# RederReverse.net
KiCad netlist of a schematic drawn in Altium Designer
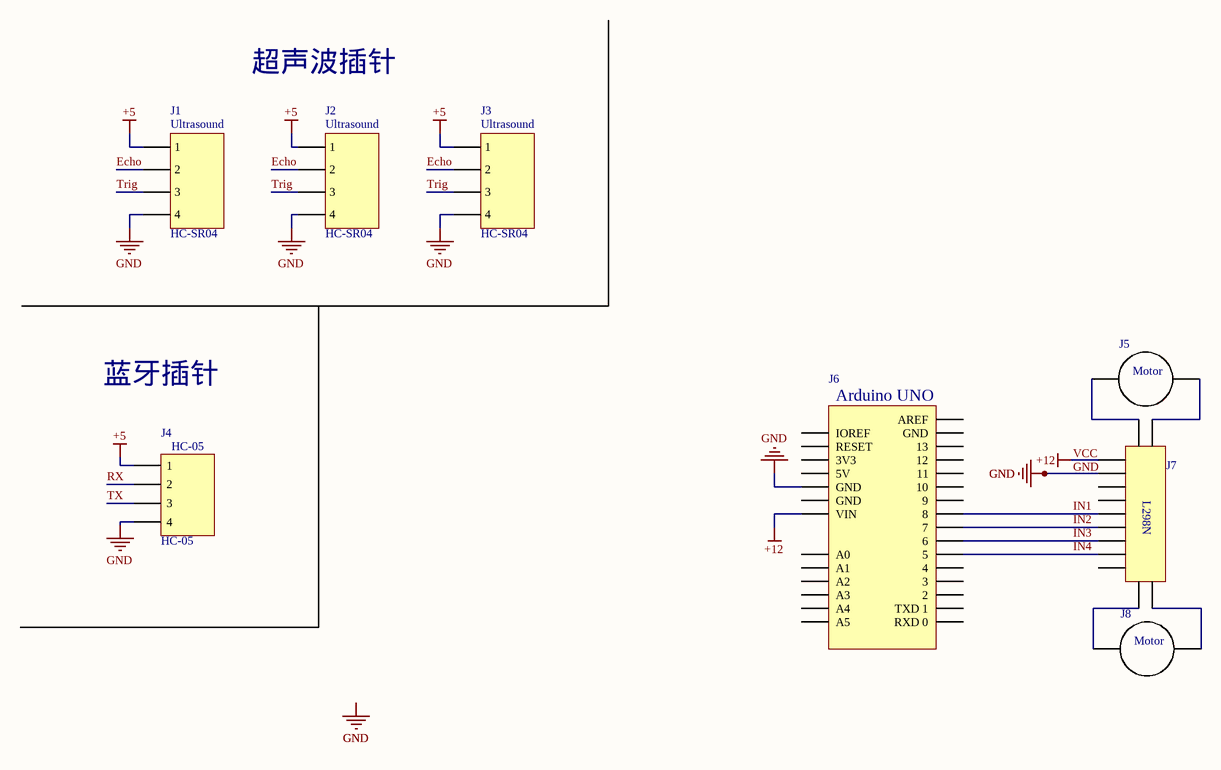
[diagram p0: RederReverse.SchDoc]

(export (version "E")
  (design (tool "Eeschema 10.0.6"))
  (components
    (comp (ref "J1")
      (value "HC-SR04")
      (description "超声波插针")
      (libsource (lib "RederReverse") (part "HC-SR04"))
    )
    (comp (ref "J2")
      (value "HC-SR04")
      (description "超声波插针")
      (libsource (lib "RederReverse") (part "HC-SR04"))
    )
    (comp (ref "J3")
      (value "HC-SR04")
      (description "超声波插针")
      (libsource (lib "RederReverse") (part "HC-SR04"))
    )
    (comp (ref "J4") (value "HC-05") (description "蓝牙插针") (libsource (lib "RederReverse") (part "HC-05")))
    (comp (ref "J5") (value "motor") (libsource (lib "RederReverse") (part "motor")))
    (comp (ref "J6") (value "A") (libsource (lib "RederReverse") (part "Arduino")))
    (comp (ref "J7") (value "L298N") (libsource (lib "RederReverse") (part "L298N")))
    (comp (ref "J8") (value "motor") (libsource (lib "RederReverse") (part "motor")))
  )
  (nets
    (net (code "1") (name "+5") (class "Default")
      (node (ref "J1") (pin "1") (pinfunction "1_1") (pintype "passive"))
      (node (ref "J2") (pin "1") (pinfunction "1_1") (pintype "passive"))
      (node (ref "J3") (pin "1") (pinfunction "1_1") (pintype "passive"))
      (node (ref "J4") (pin "1") (pinfunction "1_1") (pintype "passive"))
    )
    (net (code "2") (name "+12") (class "Default")
      (node (ref "J6") (pin "5") (pinfunction "VIN_5") (pintype "passive"))
      (node (ref "J7") (pin "4") (pinfunction "4_4") (pintype "passive"))
    )
    (net (code "3") (name "/Echo") (class "Default")
      (node (ref "J1") (pin "2") (pinfunction "2_2") (pintype "passive"))
      (node (ref "J2") (pin "2") (pinfunction "2_2") (pintype "passive"))
      (node (ref "J3") (pin "2") (pinfunction "2_2") (pintype "passive"))
    )
    (net (code "4") (name "/IN1") (class "Default")
      (node (ref "J6") (pin "14") (pinfunction "8_14") (pintype "passive"))
      (node (ref "J7") (pin "7") (pinfunction "7_7") (pintype "passive"))
    )
    (net (code "5") (name "/IN2") (class "Default")
      (node (ref "J6") (pin "13") (pinfunction "7_13") (pintype "passive"))
      (node (ref "J7") (pin "5") (pinfunction "5_5") (pintype "passive"))
    )
    (net (code "6") (name "/IN3") (class "Default")
      (node (ref "J6") (pin "12") (pinfunction "6_12") (pintype "passive"))
      (node (ref "J7") (pin "5") (pinfunction "5_5") (pintype "passive"))
    )
    (net (code "7") (name "/IN4") (class "Default")
      (node (ref "J6") (pin "11") (pinfunction "5_11") (pintype "passive"))
      (node (ref "J7") (pin "6") (pinfunction "6_6") (pintype "passive"))
    )
    (net (code "8") (name "/RX") (class "Default")
      (node (ref "J4") (pin "2") (pinfunction "2_2") (pintype "passive"))
    )
    (net (code "9") (name "/TX") (class "Default")
      (node (ref "J4") (pin "3") (pinfunction "3_3") (pintype "passive"))
    )
    (net (code "10") (name "/Trig") (class "Default")
      (node (ref "J1") (pin "3") (pinfunction "3_3") (pintype "passive"))
      (node (ref "J2") (pin "3") (pinfunction "3_3") (pintype "passive"))
      (node (ref "J3") (pin "3") (pinfunction "3_3") (pintype "passive"))
    )
    (net (code "12") (name "GND") (class "Default")
      (node (ref "J1") (pin "4") (pinfunction "4_4") (pintype "passive"))
      (node (ref "J2") (pin "4") (pinfunction "4_4") (pintype "passive"))
      (node (ref "J3") (pin "4") (pinfunction "4_4") (pintype "passive"))
      (node (ref "J4") (pin "4") (pinfunction "4_4") (pintype "passive"))
      (node (ref "J6") (pin "3") (pinfunction "GND_3") (pintype "passive"))
      (node (ref "J7") (pin "4") (pinfunction "4_4") (pintype "passive"))
    )
    (net (code "13") (name "Net-(J5-Pad1)") (class "Default")
      (node (ref "J5") (pin "1") (pinfunction "1_1") (pintype "passive"))
      (node (ref "J7") (pin "2") (pinfunction "2_2") (pintype "passive"))
    )
    (net (code "14") (name "Net-(J5-Pad2)") (class "Default")
      (node (ref "J5") (pin "2") (pinfunction "2_2") (pintype "passive"))
      (node (ref "J7") (pin "1") (pinfunction "1_1") (pintype "passive"))
    )
    (net (code "15") (name "Net-(J7-Pad3)") (class "Default")
      (node (ref "J7") (pin "3") (pinfunction "3_3") (pintype "passive"))
      (node (ref "J8") (pin "2") (pinfunction "2_2") (pintype "passive"))
    )
    (net (code "16") (name "Net-(J7-Pad4)") (class "Default")
      (node (ref "J7") (pin "4") (pinfunction "4_4") (pintype "passive"))
      (node (ref "J8") (pin "1") (pinfunction "1_1") (pintype "passive"))
    )
    (net (code "17") (name "unconnected-(J6-2-Pad8)") (class "Default")
      (node (ref "J6") (pin "8") (pinfunction "2_8") (pintype "passive"))
    )
    (net (code "18") (name "unconnected-(J6-3-Pad9)") (class "Default")
      (node (ref "J6") (pin "9") (pinfunction "3_9") (pintype "passive"))
    )
    (net (code "19") (name "unconnected-(J6-3V3-Pad4)") (class "Default")
      (node (ref "J6") (pin "4") (pinfunction "3V3_4") (pintype "passive"))
    )
    (net (code "20") (name "unconnected-(J6-4-Pad10)") (class "Default")
      (node (ref "J6") (pin "10") (pinfunction "4_10") (pintype "passive"))
    )
    (net (code "21") (name "unconnected-(J6-5V-Pad5)") (class "Default")
      (node (ref "J6") (pin "5") (pinfunction "5V_5") (pintype "passive"))
    )
    (net (code "22") (name "unconnected-(J6-9-Pad15)") (class "Default")
      (node (ref "J6") (pin "15") (pinfunction "9_15") (pintype "passive"))
    )
    (net (code "23") (name "unconnected-(J6-10-Pad16)") (class "Default")
      (node (ref "J6") (pin "16") (pinfunction "10_16") (pintype "passive"))
    )
    (net (code "24") (name "unconnected-(J6-11-Pad17)") (class "Default")
      (node (ref "J6") (pin "17") (pinfunction "11_17") (pintype "passive"))
    )
    (net (code "25") (name "unconnected-(J6-12-Pad18)") (class "Default")
      (node (ref "J6") (pin "18") (pinfunction "12_18") (pintype "passive"))
    )
    (net (code "26") (name "unconnected-(J6-13-Pad19)") (class "Default")
      (node (ref "J6") (pin "19") (pinfunction "13_19") (pintype "passive"))
    )
    (net (code "27") (name "unconnected-(J6-A0-Pad1)") (class "Default")
      (node (ref "J6") (pin "1") (pinfunction "A0_1") (pintype "passive"))
    )
    (net (code "28") (name "unconnected-(J6-A1-Pad2)") (class "Default")
      (node (ref "J6") (pin "2") (pinfunction "A1_2") (pintype "passive"))
    )
    (net (code "29") (name "unconnected-(J6-A2-Pad3)") (class "Default")
      (node (ref "J6") (pin "3") (pinfunction "A2_3") (pintype "passive"))
    )
    (net (code "30") (name "unconnected-(J6-A3-Pad4)") (class "Default")
      (node (ref "J6") (pin "4") (pinfunction "A3_4") (pintype "passive"))
    )
    (net (code "31") (name "unconnected-(J6-A4-Pad5)") (class "Default")
      (node (ref "J6") (pin "5") (pinfunction "A4_5") (pintype "passive"))
    )
    (net (code "32") (name "unconnected-(J6-A5-Pad6)") (class "Default")
      (node (ref "J6") (pin "6") (pinfunction "A5_6") (pintype "passive"))
    )
    (net (code "33") (name "unconnected-(J6-AREF-Pad21)") (class "Default")
      (node (ref "J6") (pin "21") (pinfunction "AREF_21") (pintype "passive"))
    )
    (net (code "34") (name "unconnected-(J6-GND-Pad4)") (class "Default")
      (node (ref "J6") (pin "4") (pinfunction "GND_4") (pintype "passive"))
    )
    (net (code "35") (name "unconnected-(J6-GND-Pad20)") (class "Default")
      (node (ref "J6") (pin "20") (pinfunction "GND_20") (pintype "passive"))
    )
    (net (code "36") (name "unconnected-(J6-IOREF-Pad2)") (class "Default")
      (node (ref "J6") (pin "2") (pinfunction "IOREF_2") (pintype "passive"))
    )
    (net (code "37") (name "unconnected-(J6-RESET-Pad3)") (class "Default")
      (node (ref "J6") (pin "3") (pinfunction "RESET_3") (pintype "passive"))
    )
    (net (code "38") (name "unconnected-(J6-RXD_0-Pad6)") (class "Default")
      (node (ref "J6") (pin "6") (pinfunction "RXD_0_6") (pintype "passive"))
    )
    (net (code "39") (name "unconnected-(J6-TXD_1-Pad7)") (class "Default")
      (node (ref "J6") (pin "7") (pinfunction "TXD_1_7") (pintype "passive"))
    )
    (net (code "40") (name "unconnected-(J7-Pad5)") (class "Default")
      (node (ref "J7") (pin "5") (pinfunction "5_5") (pintype "passive"))
    )
    (net (code "41") (name "unconnected-(J7-Pad6)") (class "Default")
      (node (ref "J7") (pin "6") (pinfunction "6_6") (pintype "passive"))
    )
    (net (code "42") (name "unconnected-(J7-Pad7)") (class "Default")
      (node (ref "J7") (pin "7") (pinfunction "7_7") (pintype "passive"))
    )
  )
)
